# Clocking.net
KiCad netlist of a schematic drawn in Altium Designer
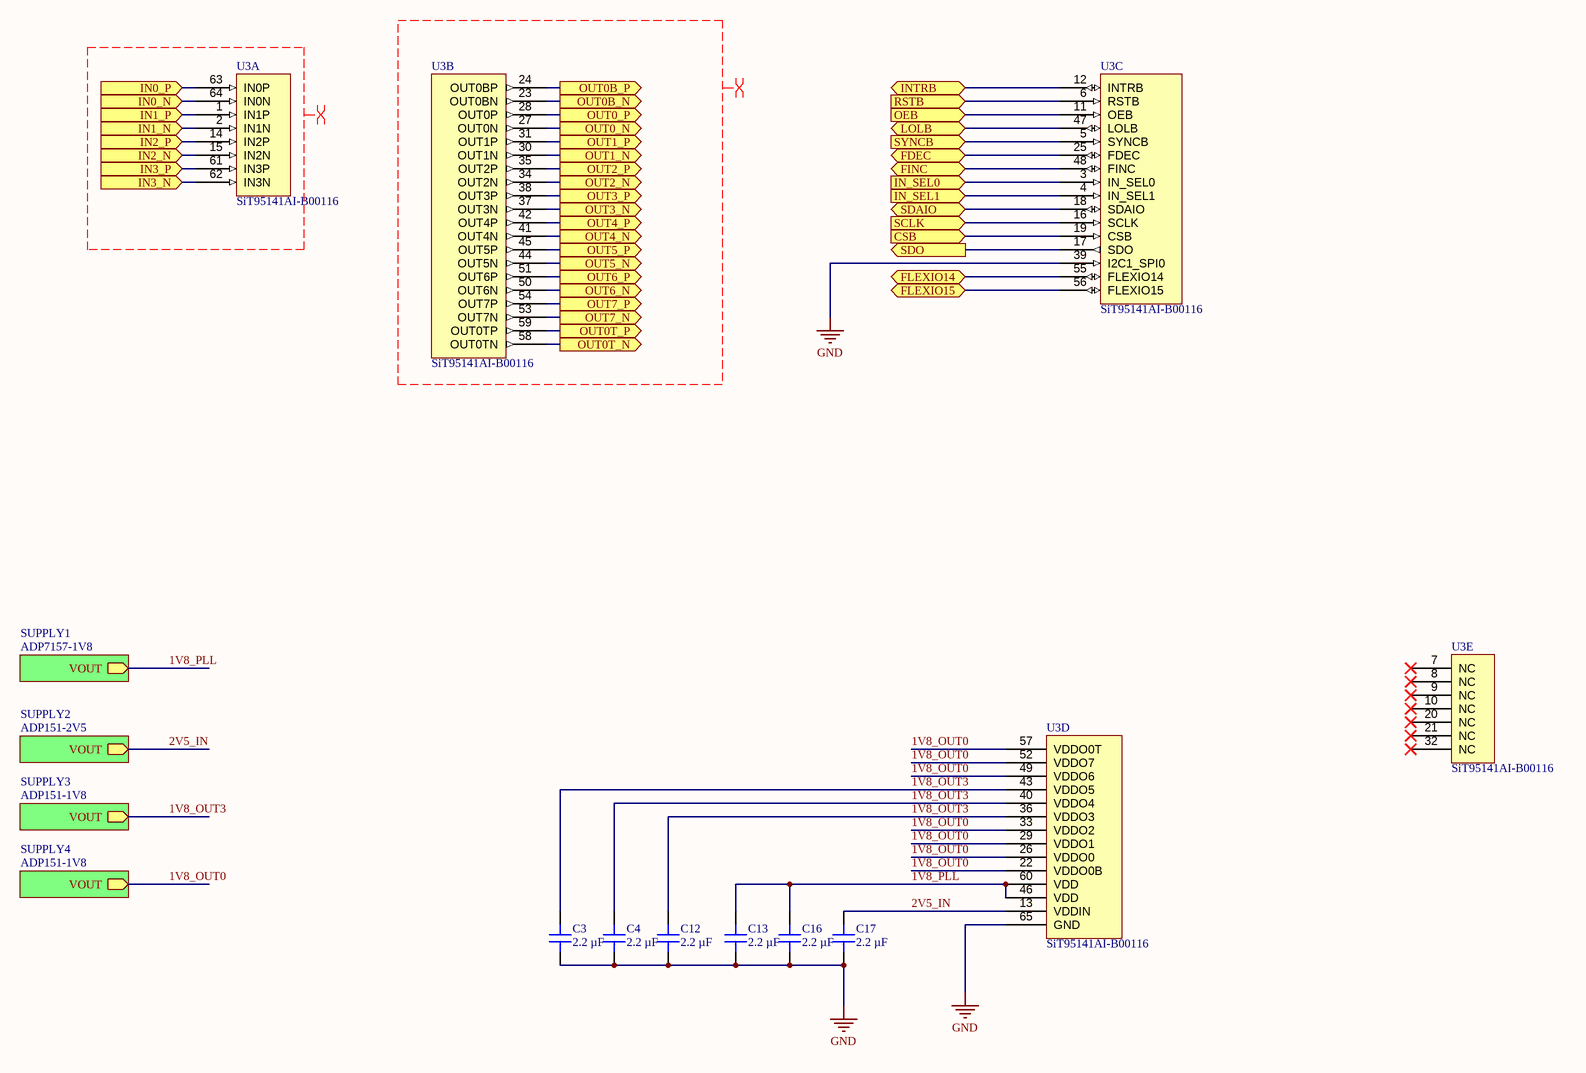
[diagram p0: Clocking.SchDoc]

(export (version "E")
  (design (tool "Eeschema 10.0.6"))
  (components
    (comp (ref "C3")
      (value "2.2 µF")
      (footprint "CAP 0201_0603")
      (description "CAP CER 2.2UF 6.3V X5R 0201")
      (fields
        (field (name "PART NUMBER") "GRM033R60J225ME15D")
        (field (name "MANUFACTURER") "Murata Electronics")
      )
      (libsource (lib "Celestial Altium Library - altium_library") (part "Capacitor"))
    )
    (comp (ref "C4")
      (value "2.2 µF")
      (footprint "CAP 0201_0603")
      (description "CAP CER 2.2UF 6.3V X5R 0201")
      (fields
        (field (name "PART NUMBER") "GRM033R60J225ME15D")
        (field (name "MANUFACTURER") "Murata Electronics")
      )
      (libsource (lib "Celestial Altium Library - altium_library") (part "Capacitor"))
    )
    (comp (ref "C12")
      (value "2.2 µF")
      (footprint "CAP 0201_0603")
      (description "CAP CER 2.2UF 6.3V X5R 0201")
      (fields
        (field (name "PART NUMBER") "GRM033R60J225ME15D")
        (field (name "MANUFACTURER") "Murata Electronics")
      )
      (libsource (lib "Celestial Altium Library - altium_library") (part "Capacitor"))
    )
    (comp (ref "C13")
      (value "2.2 µF")
      (footprint "CAP 0201_0603")
      (description "CAP CER 2.2UF 6.3V X5R 0201")
      (fields
        (field (name "PART NUMBER") "GRM033R60J225ME15D")
        (field (name "MANUFACTURER") "Murata Electronics")
      )
      (libsource (lib "Celestial Altium Library - altium_library") (part "Capacitor"))
    )
    (comp (ref "C16")
      (value "2.2 µF")
      (footprint "CAP 0201_0603")
      (description "CAP CER 2.2UF 6.3V X5R 0201")
      (fields
        (field (name "PART NUMBER") "GRM033R60J225ME15D")
        (field (name "MANUFACTURER") "Murata Electronics")
      )
      (libsource (lib "Celestial Altium Library - altium_library") (part "Capacitor"))
    )
    (comp (ref "C17")
      (value "2.2 µF")
      (footprint "CAP 0201_0603")
      (description "CAP CER 2.2UF 6.3V X5R 0201")
      (fields
        (field (name "PART NUMBER") "GRM033R60J225ME15D")
        (field (name "MANUFACTURER") "Murata Electronics")
      )
      (libsource (lib "Celestial Altium Library - altium_library") (part "Capacitor"))
    )
    (comp (ref "U3")
      (value "SiT95141AI-B00116")
      (footprint "QFN50P900X900X90_HS-65N")
      (libsource (lib "SimulaVR") (part "SiT95141AI-B00116-Symbol-1"))
    )
  )
  (nets
    (net (code "1") (name "/1V8_OUT0") (class "Default")
      (node (ref "U3") (pin "22") (pinfunction "VDDO0B_22") (pintype "power_in"))
      (node (ref "U3") (pin "26") (pinfunction "VDDO0_26") (pintype "power_in"))
      (node (ref "U3") (pin "29") (pinfunction "VDDO1_29") (pintype "power_in"))
      (node (ref "U3") (pin "33") (pinfunction "VDDO2_33") (pintype "power_in"))
      (node (ref "U3") (pin "49") (pinfunction "VDDO6_49") (pintype "power_in"))
      (node (ref "U3") (pin "52") (pinfunction "VDDO7_52") (pintype "power_in"))
      (node (ref "U3") (pin "57") (pinfunction "VDDO0T_57") (pintype "power_in"))
    )
    (net (code "2") (name "/1V8_OUT3") (class "Default")
      (node (ref "C12") (pin "2") (pinfunction "2_2") (pintype "passive"))
      (node (ref "C3") (pin "2") (pinfunction "2_2") (pintype "passive"))
      (node (ref "C4") (pin "2") (pinfunction "2_2") (pintype "passive"))
      (node (ref "U3") (pin "36") (pinfunction "VDDO3_36") (pintype "power_in"))
      (node (ref "U3") (pin "40") (pinfunction "VDDO4_40") (pintype "power_in"))
      (node (ref "U3") (pin "43") (pinfunction "VDDO5_43") (pintype "power_in"))
    )
    (net (code "3") (name "/1V8_PLL") (class "Default")
      (node (ref "C13") (pin "2") (pinfunction "2_2") (pintype "passive"))
      (node (ref "C16") (pin "2") (pinfunction "2_2") (pintype "passive"))
      (node (ref "U3") (pin "46") (pinfunction "VDD_46") (pintype "power_in"))
      (node (ref "U3") (pin "60") (pinfunction "VDD_60") (pintype "power_in"))
    )
    (net (code "4") (name "/2V5_IN") (class "Default")
      (node (ref "C17") (pin "2") (pinfunction "2_2") (pintype "passive"))
      (node (ref "U3") (pin "13") (pinfunction "VDDIN_13") (pintype "power_in"))
    )
    (net (code "5") (name "/CSB") (class "Default")
      (node (ref "U3") (pin "19") (pinfunction "CSB_19") (pintype "input"))
    )
    (net (code "6") (name "/FDEC") (class "Default")
      (node (ref "U3") (pin "25") (pinfunction "FDEC_25") (pintype "bidirectional"))
    )
    (net (code "7") (name "/FINC") (class "Default")
      (node (ref "U3") (pin "48") (pinfunction "FINC_48") (pintype "bidirectional"))
    )
    (net (code "8") (name "/FLEXIO14") (class "Default")
      (node (ref "U3") (pin "55") (pinfunction "FLEXIO14_55") (pintype "bidirectional"))
    )
    (net (code "9") (name "/FLEXIO15") (class "Default")
      (node (ref "U3") (pin "56") (pinfunction "FLEXIO15_56") (pintype "bidirectional"))
    )
    (net (code "10") (name "/IN0_N") (class "Default")
      (node (ref "U3") (pin "64") (pinfunction "IN0N_64") (pintype "input"))
    )
    (net (code "11") (name "/IN0_P") (class "Default")
      (node (ref "U3") (pin "63") (pinfunction "IN0P_63") (pintype "input"))
    )
    (net (code "12") (name "/IN1_N") (class "Default")
      (node (ref "U3") (pin "2") (pinfunction "IN1N_2") (pintype "input"))
    )
    (net (code "13") (name "/IN1_P") (class "Default")
      (node (ref "U3") (pin "1") (pinfunction "IN1P_1") (pintype "input"))
    )
    (net (code "14") (name "/IN2_N") (class "Default")
      (node (ref "U3") (pin "15") (pinfunction "IN2N_15") (pintype "input"))
    )
    (net (code "15") (name "/IN2_P") (class "Default")
      (node (ref "U3") (pin "14") (pinfunction "IN2P_14") (pintype "input"))
    )
    (net (code "16") (name "/IN3_N") (class "Default")
      (node (ref "U3") (pin "62") (pinfunction "IN3N_62") (pintype "input"))
    )
    (net (code "17") (name "/IN3_P") (class "Default")
      (node (ref "U3") (pin "61") (pinfunction "IN3P_61") (pintype "input"))
    )
    (net (code "18") (name "/INTRB") (class "Default")
      (node (ref "U3") (pin "12") (pinfunction "INTRB_12") (pintype "bidirectional"))
    )
    (net (code "19") (name "/IN_SEL0") (class "Default")
      (node (ref "U3") (pin "3") (pinfunction "IN_SEL0_3") (pintype "input"))
    )
    (net (code "20") (name "/IN_SEL1") (class "Default")
      (node (ref "U3") (pin "4") (pinfunction "IN_SEL1_4") (pintype "input"))
    )
    (net (code "21") (name "/LOLB") (class "Default")
      (node (ref "U3") (pin "47") (pinfunction "LOLB_47") (pintype "bidirectional"))
    )
    (net (code "22") (name "/OEB") (class "Default")
      (node (ref "U3") (pin "11") (pinfunction "OEB_11") (pintype "input"))
    )
    (net (code "23") (name "/OUT0B_N") (class "Default")
      (node (ref "U3") (pin "23") (pinfunction "OUT0BN_23") (pintype "output"))
    )
    (net (code "24") (name "/OUT0B_P") (class "Default")
      (node (ref "U3") (pin "24") (pinfunction "OUT0BP_24") (pintype "output"))
    )
    (net (code "25") (name "/OUT0T_N") (class "Default")
      (node (ref "U3") (pin "58") (pinfunction "OUT0TN_58") (pintype "output"))
    )
    (net (code "26") (name "/OUT0T_P") (class "Default")
      (node (ref "U3") (pin "59") (pinfunction "OUT0TP_59") (pintype "output"))
    )
    (net (code "27") (name "/OUT0_N") (class "Default")
      (node (ref "U3") (pin "27") (pinfunction "OUT0N_27") (pintype "output"))
    )
    (net (code "28") (name "/OUT0_P") (class "Default")
      (node (ref "U3") (pin "28") (pinfunction "OUT0P_28") (pintype "output"))
    )
    (net (code "29") (name "/OUT1_N") (class "Default")
      (node (ref "U3") (pin "30") (pinfunction "OUT1N_30") (pintype "output"))
    )
    (net (code "30") (name "/OUT1_P") (class "Default")
      (node (ref "U3") (pin "31") (pinfunction "OUT1P_31") (pintype "output"))
    )
    (net (code "31") (name "/OUT2_N") (class "Default")
      (node (ref "U3") (pin "34") (pinfunction "OUT2N_34") (pintype "output"))
    )
    (net (code "32") (name "/OUT2_P") (class "Default")
      (node (ref "U3") (pin "35") (pinfunction "OUT2P_35") (pintype "output"))
    )
    (net (code "33") (name "/OUT3_N") (class "Default")
      (node (ref "U3") (pin "37") (pinfunction "OUT3N_37") (pintype "output"))
    )
    (net (code "34") (name "/OUT3_P") (class "Default")
      (node (ref "U3") (pin "38") (pinfunction "OUT3P_38") (pintype "output"))
    )
    (net (code "35") (name "/OUT4_N") (class "Default")
      (node (ref "U3") (pin "41") (pinfunction "OUT4N_41") (pintype "output"))
    )
    (net (code "36") (name "/OUT4_P") (class "Default")
      (node (ref "U3") (pin "42") (pinfunction "OUT4P_42") (pintype "output"))
    )
    (net (code "37") (name "/OUT5_N") (class "Default")
      (node (ref "U3") (pin "44") (pinfunction "OUT5N_44") (pintype "output"))
    )
    (net (code "38") (name "/OUT5_P") (class "Default")
      (node (ref "U3") (pin "45") (pinfunction "OUT5P_45") (pintype "output"))
    )
    (net (code "39") (name "/OUT6_N") (class "Default")
      (node (ref "U3") (pin "50") (pinfunction "OUT6N_50") (pintype "output"))
    )
    (net (code "40") (name "/OUT6_P") (class "Default")
      (node (ref "U3") (pin "51") (pinfunction "OUT6P_51") (pintype "output"))
    )
    (net (code "41") (name "/OUT7_N") (class "Default")
      (node (ref "U3") (pin "53") (pinfunction "OUT7N_53") (pintype "output"))
    )
    (net (code "42") (name "/OUT7_P") (class "Default")
      (node (ref "U3") (pin "54") (pinfunction "OUT7P_54") (pintype "output"))
    )
    (net (code "43") (name "/RSTB") (class "Default")
      (node (ref "U3") (pin "6") (pinfunction "RSTB_6") (pintype "input"))
    )
    (net (code "44") (name "/SCLK") (class "Default")
      (node (ref "U3") (pin "16") (pinfunction "SCLK_16") (pintype "input"))
    )
    (net (code "45") (name "/SDAIO") (class "Default")
      (node (ref "U3") (pin "18") (pinfunction "SDAIO_18") (pintype "bidirectional"))
    )
    (net (code "46") (name "/SDO") (class "Default")
      (node (ref "U3") (pin "17") (pinfunction "SDO_17") (pintype "output"))
    )
    (net (code "47") (name "/SYNCB") (class "Default")
      (node (ref "U3") (pin "5") (pinfunction "SYNCB_5") (pintype "input"))
    )
    (net (code "48") (name "GND") (class "Default")
      (node (ref "C12") (pin "1") (pinfunction "1_1") (pintype "passive"))
      (node (ref "C13") (pin "1") (pinfunction "1_1") (pintype "passive"))
      (node (ref "C16") (pin "1") (pinfunction "1_1") (pintype "passive"))
      (node (ref "C17") (pin "1") (pinfunction "1_1") (pintype "passive"))
      (node (ref "C3") (pin "1") (pinfunction "1_1") (pintype "passive"))
      (node (ref "C4") (pin "1") (pinfunction "1_1") (pintype "passive"))
      (node (ref "U3") (pin "39") (pinfunction "I2C1_SPI0_39") (pintype "input"))
      (node (ref "U3") (pin "65") (pinfunction "GND_65") (pintype "power_in"))
    )
    (net (code "49") (name "unconnected-(U3E-NC-Pad7)") (class "Default")
      (node (ref "U3") (pin "7") (pinfunction "NC_7") (pintype "passive+no_connect"))
    )
    (net (code "50") (name "unconnected-(U3E-NC-Pad8)") (class "Default")
      (node (ref "U3") (pin "8") (pinfunction "NC_8") (pintype "passive+no_connect"))
    )
    (net (code "51") (name "unconnected-(U3E-NC-Pad9)") (class "Default")
      (node (ref "U3") (pin "9") (pinfunction "NC_9") (pintype "passive+no_connect"))
    )
    (net (code "52") (name "unconnected-(U3E-NC-Pad10)") (class "Default")
      (node (ref "U3") (pin "10") (pinfunction "NC_10") (pintype "passive+no_connect"))
    )
    (net (code "53") (name "unconnected-(U3E-NC-Pad20)") (class "Default")
      (node (ref "U3") (pin "20") (pinfunction "NC_20") (pintype "passive+no_connect"))
    )
    (net (code "54") (name "unconnected-(U3E-NC-Pad21)") (class "Default")
      (node (ref "U3") (pin "21") (pinfunction "NC_21") (pintype "passive+no_connect"))
    )
    (net (code "55") (name "unconnected-(U3E-NC-Pad32)") (class "Default")
      (node (ref "U3") (pin "32") (pinfunction "NC_32") (pintype "passive+no_connect"))
    )
  )
)
